# Probe.net
KiCad netlist of a schematic drawn in Altium Designer
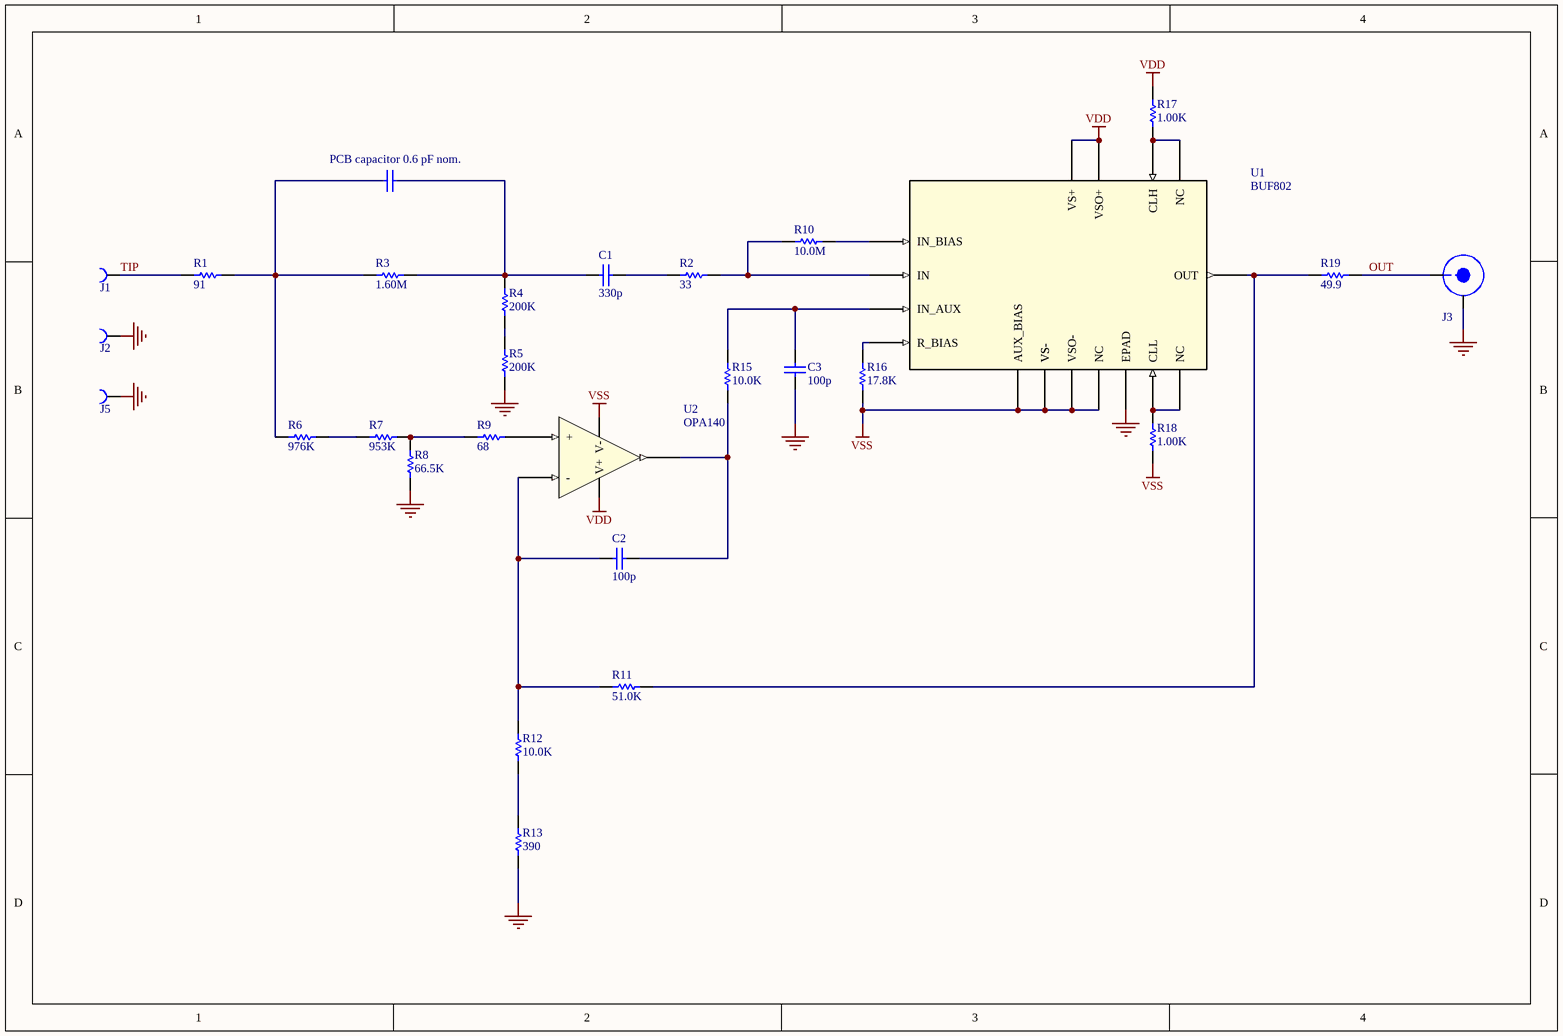
[diagram p0: Probe.SchDoc]

(export (version "E")
  (design (tool "Eeschema 10.0.6"))
  (components
    (comp (ref "C1")
      (value "330p")
      (footprint "CAPC0402(1005)50_M")
      (description "CAP CER 330PF±5% 50V C0G 0402")
      (fields
        (field (name "MANUFACTURER") "Murata")
        (field (name "MANUFACTURER PART NUMBER") "GRM1555C1H331JA01D")
      )
      (libsource (lib "Murata GRM 0402") (part "Capacitor_Generic"))
    )
    (comp (ref "C2")
      (value "100p")
      (footprint "CAPC0402(1005)50_M")
      (description "CAP CER 100PF±5% 50V C0G 0402")
      (fields
        (field (name "MANUFACTURER") "Samsung Electro-Mechanics")
        (field (name "MANUFACTURER PART NUMBER") "CL05C101JB5NNNC")
      )
      (libsource (lib "Samsung CAPC0402") (part "Capacitor_Generic"))
    )
    (comp (ref "C3")
      (value "100p")
      (footprint "CAPC0402(1005)50_M")
      (description "CAP CER 100PF±5% 50V C0G 0402")
      (fields
        (field (name "MANUFACTURER") "Samsung Electro-Mechanics")
        (field (name "MANUFACTURER PART NUMBER") "CL05C101JB5NNNC")
      )
      (libsource (lib "Samsung CAPC0402") (part "Capacitor_Generic"))
    )
    (comp (ref "J1")
      (value "0339-0-15-01-15-27-10-0")
      (footprint "MILL-MAX 0339")
      (description "CONN PIN RCPT")
      (fields (field (name "MANUFACTURER") "Mill-Max"))
      (libsource (lib "Connectors") (part "0339-0-15-01-15-27-10-0"))
    )
    (comp (ref "J2")
      (value "0339-0-15-01-15-27-10-0")
      (footprint "MILL-MAX 0339")
      (description "CONN PIN RCPT")
      (fields (field (name "MANUFACTURER") "Mill-Max"))
      (libsource (lib "Connectors") (part "0339-0-15-01-15-27-10-0"))
    )
    (comp (ref "J3")
      (value "901-10511-3")
      (footprint "901-10511-3")
      (description "CONN SMA JACK STR 50OHM EDGE MNT")
      (fields (field (name "MANUFACTURER") "Amphenol RF"))
      (libsource (lib "Connectors") (part "901-10511-3"))
    )
    (comp (ref "J5")
      (value "0339-0-15-01-15-27-10-0")
      (footprint "MILL-MAX 0339")
      (description "CONN PIN RCPT")
      (fields (field (name "MANUFACTURER") "Mill-Max"))
      (libsource (lib "Connectors") (part "0339-0-15-01-15-27-10-0"))
    )
    (comp (ref "R1")
      (value "91")
      (footprint "RESC0402(1005)_M")
      (description "RES 91 OHM 1% 1/16W 0402")
      (fields (field (name "PART NUMBER") "RESC0402-91R0-1pct"))
      (libsource (lib "R0402 - 1pct") (part "Resistor_Generic"))
    )
    (comp (ref "R2")
      (value "33")
      (footprint "RESC0402(1005)_M")
      (description "RES 33 OHM 1% 1/16W 0402")
      (fields (field (name "PART NUMBER") "RESC0402-33R0-1pct"))
      (libsource (lib "R0402 - 1pct") (part "Resistor_Generic"))
    )
    (comp (ref "R3")
      (value "1.60M")
      (footprint "RESC0402(1005)_M")
      (description "RES 1.60M OHM 1% 1/16W 0402")
      (fields (field (name "PART NUMBER") "RESC0402-1M60-1pct"))
      (libsource (lib "R0402 - 1pct") (part "Resistor_Generic"))
    )
    (comp (ref "R4")
      (value "200K")
      (footprint "RESC0402(1005)_M")
      (description "RES 200K OHM 1% 1/16W 0402")
      (fields (field (name "PART NUMBER") "RESC0402-200K-1pct"))
      (libsource (lib "R0402 - 1pct") (part "Resistor_Generic"))
    )
    (comp (ref "R5")
      (value "200K")
      (footprint "RESC0402(1005)_M")
      (description "RES 200K OHM 1% 1/16W 0402")
      (fields (field (name "PART NUMBER") "RESC0402-200K-1pct"))
      (libsource (lib "R0402 - 1pct") (part "Resistor_Generic"))
    )
    (comp (ref "R6")
      (value "976K")
      (footprint "RESC0402(1005)_M")
      (description "RES 976K OHM 1% 1/16W 0402")
      (fields (field (name "PART NUMBER") "RESC0402-976K-1pct"))
      (libsource (lib "R0402 - 1pct") (part "Resistor_Generic"))
    )
    (comp (ref "R7")
      (value "953K")
      (footprint "RESC0402(1005)_M")
      (description "RES 953K OHM 1% 1/16W 0402")
      (fields (field (name "PART NUMBER") "RESC0402-953K-1pct"))
      (libsource (lib "R0402 - 1pct") (part "Resistor_Generic"))
    )
    (comp (ref "R8")
      (value "66.5K")
      (footprint "RESC0402(1005)_M")
      (description "RES 66.5K OHM 1% 1/16W 0402")
      (fields (field (name "PART NUMBER") "RESC0402-66K5-1pct"))
      (libsource (lib "R0402 - 1pct") (part "Resistor_Generic"))
    )
    (comp (ref "R9")
      (value "68")
      (footprint "RESC0402(1005)_M")
      (description "RES 68 OHM 1% 1/16W 0402")
      (fields (field (name "PART NUMBER") "RESC0402-68R0-1pct"))
      (libsource (lib "R0402 - 1pct") (part "Resistor_Generic"))
    )
    (comp (ref "R10")
      (value "10.0M")
      (footprint "RESC0402(1005)_M")
      (description "RES 10.0M OHM 1% 1/16W 0402")
      (fields (field (name "PART NUMBER") "RESC0402-10M0-1pct"))
      (libsource (lib "R0402 - 1pct") (part "Resistor_Generic"))
    )
    (comp (ref "R11")
      (value "51.0K")
      (footprint "RESC0402(1005)_M")
      (description "RES 51.0K OHM 1% 1/16W 0402")
      (fields (field (name "PART NUMBER") "RESC0402-51K0-1pct"))
      (libsource (lib "R0402 - 1pct") (part "Resistor_Generic"))
    )
    (comp (ref "R12")
      (value "10.0K")
      (footprint "RESC0402(1005)_M")
      (description "RES 10.0K OHM 1% 1/16W 0402")
      (fields (field (name "PART NUMBER") "RESC0402-10K0-1pct"))
      (libsource (lib "R0402 - 1pct") (part "Resistor_Generic"))
    )
    (comp (ref "R13")
      (value "390")
      (footprint "RESC0402(1005)_M")
      (description "RES 390 OHM 1% 1/16W 0402")
      (fields (field (name "PART NUMBER") "RESC0402-390R-1pct"))
      (libsource (lib "R0402 - 1pct") (part "Resistor_Generic"))
    )
    (comp (ref "R15")
      (value "10.0K")
      (footprint "RESC0402(1005)_M")
      (description "RES 10.0K OHM 1% 1/16W 0402")
      (fields (field (name "PART NUMBER") "RESC0402-10K0-1pct"))
      (libsource (lib "R0402 - 1pct") (part "Resistor_Generic"))
    )
    (comp (ref "R16")
      (value "17.8K")
      (footprint "RESC0402(1005)_M")
      (description "RES 17.8K OHM 1% 1/16W 0402")
      (fields (field (name "PART NUMBER") "RESC0402-17K8-1pct"))
      (libsource (lib "R0402 - 1pct") (part "Resistor_Generic"))
    )
    (comp (ref "R17")
      (value "1.00K")
      (footprint "RESC0402(1005)_M")
      (description "RES 1.00K OHM 1% 1/16W 0402")
      (fields (field (name "PART NUMBER") "RESC0402-1K00-1pct"))
      (libsource (lib "R0402 - 1pct") (part "Resistor_Generic"))
    )
    (comp (ref "R18")
      (value "1.00K")
      (footprint "RESC0402(1005)_M")
      (description "RES 1.00K OHM 1% 1/16W 0402")
      (fields (field (name "PART NUMBER") "RESC0402-1K00-1pct"))
      (libsource (lib "R0402 - 1pct") (part "Resistor_Generic"))
    )
    (comp (ref "R19")
      (value "49.9")
      (footprint "RESC0402(1005)_M")
      (description "RES 49.9 OHM 1% 1/16W 0402")
      (fields (field (name "PART NUMBER") "RESC0402-49R9-1pct"))
      (libsource (lib "R0402 - 1pct") (part "Resistor_Generic"))
    )
    (comp (ref "U1")
      (value "BUF802")
      (footprint "VQFN16_RGT_TEX- OSHPARK")
      (description "WIDE-BANDWIDTH JFET BUFFER")
      (fields
        (field (name "MANUFACTURER") "Texas Instruments")
        (field (name "MANUFACTURER PART NUMBER") "BUF802IRGTR")
      )
      (libsource (lib "IC") (part "BUF802IRGTR"))
    )
    (comp (ref "U2")
      (value "OPA140")
      (footprint "SOIC-8")
      (description "IC OPAMP JFET 1 CIRCUIT 8SOIC")
      (fields
        (field (name "MANUFACTURER") "Texas Instruments")
        (field (name "MANUFACTURER PART NUMBER") "OPA140AIDR")
      )
      (libsource (lib "IC") (part "OPA140AIDR"))
    )
  )
  (nets
    (net (code "1") (name "/OUT") (class "Default")
      (node (ref "J3") (pin "1") (pinfunction "1_1") (pintype "passive"))
      (node (ref "R19") (pin "2") (pinfunction "2_2") (pintype "passive"))
    )
    (net (code "2") (name "/TIP") (class "Default")
      (node (ref "J1") (pin "1") (pinfunction "1_1") (pintype "passive"))
      (node (ref "R1") (pin "1") (pinfunction "1_1") (pintype "passive"))
    )
    (net (code "3") (name "GND") (class "Default")
      (node (ref "C3") (pin "2") (pinfunction "2_2") (pintype "passive"))
      (node (ref "J2") (pin "1") (pinfunction "1_1") (pintype "passive"))
      (node (ref "J3") (pin "2") (pinfunction "2_2") (pintype "passive"))
      (node (ref "J5") (pin "1") (pinfunction "1_1") (pintype "passive"))
      (node (ref "R13") (pin "2") (pinfunction "2_2") (pintype "passive"))
      (node (ref "R5") (pin "2") (pinfunction "2_2") (pintype "passive"))
      (node (ref "R8") (pin "2") (pinfunction "2_2") (pintype "passive"))
      (node (ref "U1") (pin "17") (pinfunction "EPAD_17") (pintype "passive"))
    )
    (net (code "4") (name "Net-(C1-Pad1)") (class "Default")
      (node (ref "C1") (pin "1") (pinfunction "1_1") (pintype "passive"))
      (node (ref "R3") (pin "2") (pinfunction "2_2") (pintype "passive"))
      (node (ref "R4") (pin "1") (pinfunction "1_1") (pintype "passive"))
    )
    (net (code "5") (name "Net-(C1-Pad2)") (class "Default")
      (node (ref "C1") (pin "2") (pinfunction "2_2") (pintype "passive"))
      (node (ref "R2") (pin "1") (pinfunction "1_1") (pintype "passive"))
    )
    (net (code "6") (name "Net-(R1-Pad2)") (class "Default")
      (node (ref "R1") (pin "2") (pinfunction "2_2") (pintype "passive"))
      (node (ref "R3") (pin "1") (pinfunction "1_1") (pintype "passive"))
      (node (ref "R6") (pin "1") (pinfunction "1_1") (pintype "passive"))
    )
    (net (code "7") (name "Net-(R4-Pad2)") (class "Default")
      (node (ref "R4") (pin "2") (pinfunction "2_2") (pintype "passive"))
      (node (ref "R5") (pin "1") (pinfunction "1_1") (pintype "passive"))
    )
    (net (code "8") (name "Net-(R6-Pad2)") (class "Default")
      (node (ref "R6") (pin "2") (pinfunction "2_2") (pintype "passive"))
      (node (ref "R7") (pin "1") (pinfunction "1_1") (pintype "passive"))
    )
    (net (code "9") (name "Net-(R7-Pad2)") (class "Default")
      (node (ref "R7") (pin "2") (pinfunction "2_2") (pintype "passive"))
      (node (ref "R8") (pin "1") (pinfunction "1_1") (pintype "passive"))
      (node (ref "R9") (pin "1") (pinfunction "1_1") (pintype "passive"))
    )
    (net (code "10") (name "Net-(R12-Pad2)") (class "Default")
      (node (ref "R12") (pin "2") (pinfunction "2_2") (pintype "passive"))
      (node (ref "R13") (pin "1") (pinfunction "1_1") (pintype "passive"))
    )
    (net (code "11") (name "Net-(U1-CLH)") (class "Default")
      (node (ref "R17") (pin "1") (pinfunction "1_1") (pintype "passive"))
      (node (ref "U1") (pin "15") (pinfunction "CLH_15") (pintype "input"))
      (node (ref "U1") (pin "16") (pinfunction "NC_16") (pintype "passive"))
    )
    (net (code "12") (name "Net-(U1-CLL)") (class "Default")
      (node (ref "R18") (pin "1") (pinfunction "1_1") (pintype "passive"))
      (node (ref "U1") (pin "13") (pinfunction "NC_13") (pintype "passive"))
      (node (ref "U1") (pin "14") (pinfunction "CLL_14") (pintype "input"))
    )
    (net (code "13") (name "Net-(U1-IN)") (class "Default")
      (node (ref "R10") (pin "1") (pinfunction "1_1") (pintype "passive"))
      (node (ref "R2") (pin "2") (pinfunction "2_2") (pintype "passive"))
      (node (ref "U1") (pin "2") (pinfunction "IN_2") (pintype "input"))
    )
    (net (code "14") (name "Net-(U1-IN_AUX)") (class "Default")
      (node (ref "C3") (pin "1") (pinfunction "1_1") (pintype "passive"))
      (node (ref "R15") (pin "1") (pinfunction "1_1") (pintype "passive"))
      (node (ref "U1") (pin "4") (pinfunction "IN_AUX_4") (pintype "input"))
    )
    (net (code "15") (name "Net-(U1-IN_BIAS)") (class "Default")
      (node (ref "R10") (pin "2") (pinfunction "2_2") (pintype "passive"))
      (node (ref "U1") (pin "3") (pinfunction "IN_BIAS_3") (pintype "input"))
    )
    (net (code "16") (name "Net-(U1-OUT)") (class "Default")
      (node (ref "R11") (pin "2") (pinfunction "2_2") (pintype "passive"))
      (node (ref "R19") (pin "1") (pinfunction "1_1") (pintype "passive"))
      (node (ref "U1") (pin "11") (pinfunction "OUT_11") (pintype "output"))
    )
    (net (code "17") (name "Net-(U1-R_BIAS)") (class "Default")
      (node (ref "R16") (pin "1") (pinfunction "1_1") (pintype "passive"))
      (node (ref "U1") (pin "7") (pinfunction "R_BIAS_7") (pintype "input"))
    )
    (net (code "18") (name "Net-(U2-+)") (class "Default")
      (node (ref "R9") (pin "2") (pinfunction "2_2") (pintype "passive"))
      (node (ref "U2") (pin "3") (pinfunction "+_3") (pintype "input"))
    )
    (net (code "19") (name "Net-(U2--)") (class "Default")
      (node (ref "C2") (pin "1") (pinfunction "1_1") (pintype "passive"))
      (node (ref "R11") (pin "1") (pinfunction "1_1") (pintype "passive"))
      (node (ref "R12") (pin "1") (pinfunction "1_1") (pintype "passive"))
      (node (ref "U2") (pin "2") (pinfunction "-_2") (pintype "input"))
    )
    (net (code "20") (name "Net-(U2-OUT)") (class "Default")
      (node (ref "C2") (pin "2") (pinfunction "2_2") (pintype "passive"))
      (node (ref "R15") (pin "2") (pinfunction "2_2") (pintype "passive"))
      (node (ref "U2") (pin "6") (pinfunction "OUT_6") (pintype "output"))
    )
    (net (code "21") (name "VDD") (class "Default")
      (node (ref "R17") (pin "2") (pinfunction "2_2") (pintype "passive"))
      (node (ref "U1") (pin "1") (pinfunction "VS+_1") (pintype "power_in"))
      (node (ref "U1") (pin "12") (pinfunction "VSO+_12") (pintype "power_in"))
      (node (ref "U2") (pin "7") (pinfunction "V+_7") (pintype "power_in"))
    )
    (net (code "22") (name "VSS") (class "Default")
      (node (ref "R16") (pin "2") (pinfunction "2_2") (pintype "passive"))
      (node (ref "R18") (pin "2") (pinfunction "2_2") (pintype "passive"))
      (node (ref "U1") (pin "10") (pinfunction "VSO-_10") (pintype "power_in"))
      (node (ref "U1") (pin "5") (pinfunction "VS-_5") (pintype "power_in"))
      (node (ref "U1") (pin "6") (pinfunction "AUX_BIAS_6") (pintype "power_in"))
      (node (ref "U1") (pin "8") (pinfunction "VS-_8") (pintype "power_in"))
      (node (ref "U1") (pin "9") (pinfunction "NC_9") (pintype "passive"))
      (node (ref "U2") (pin "4") (pinfunction "V-_4") (pintype "power_in"))
    )
  )
)
